# 05_kbd_pm.net
KiCad netlist of a schematic drawn in Altium Designer
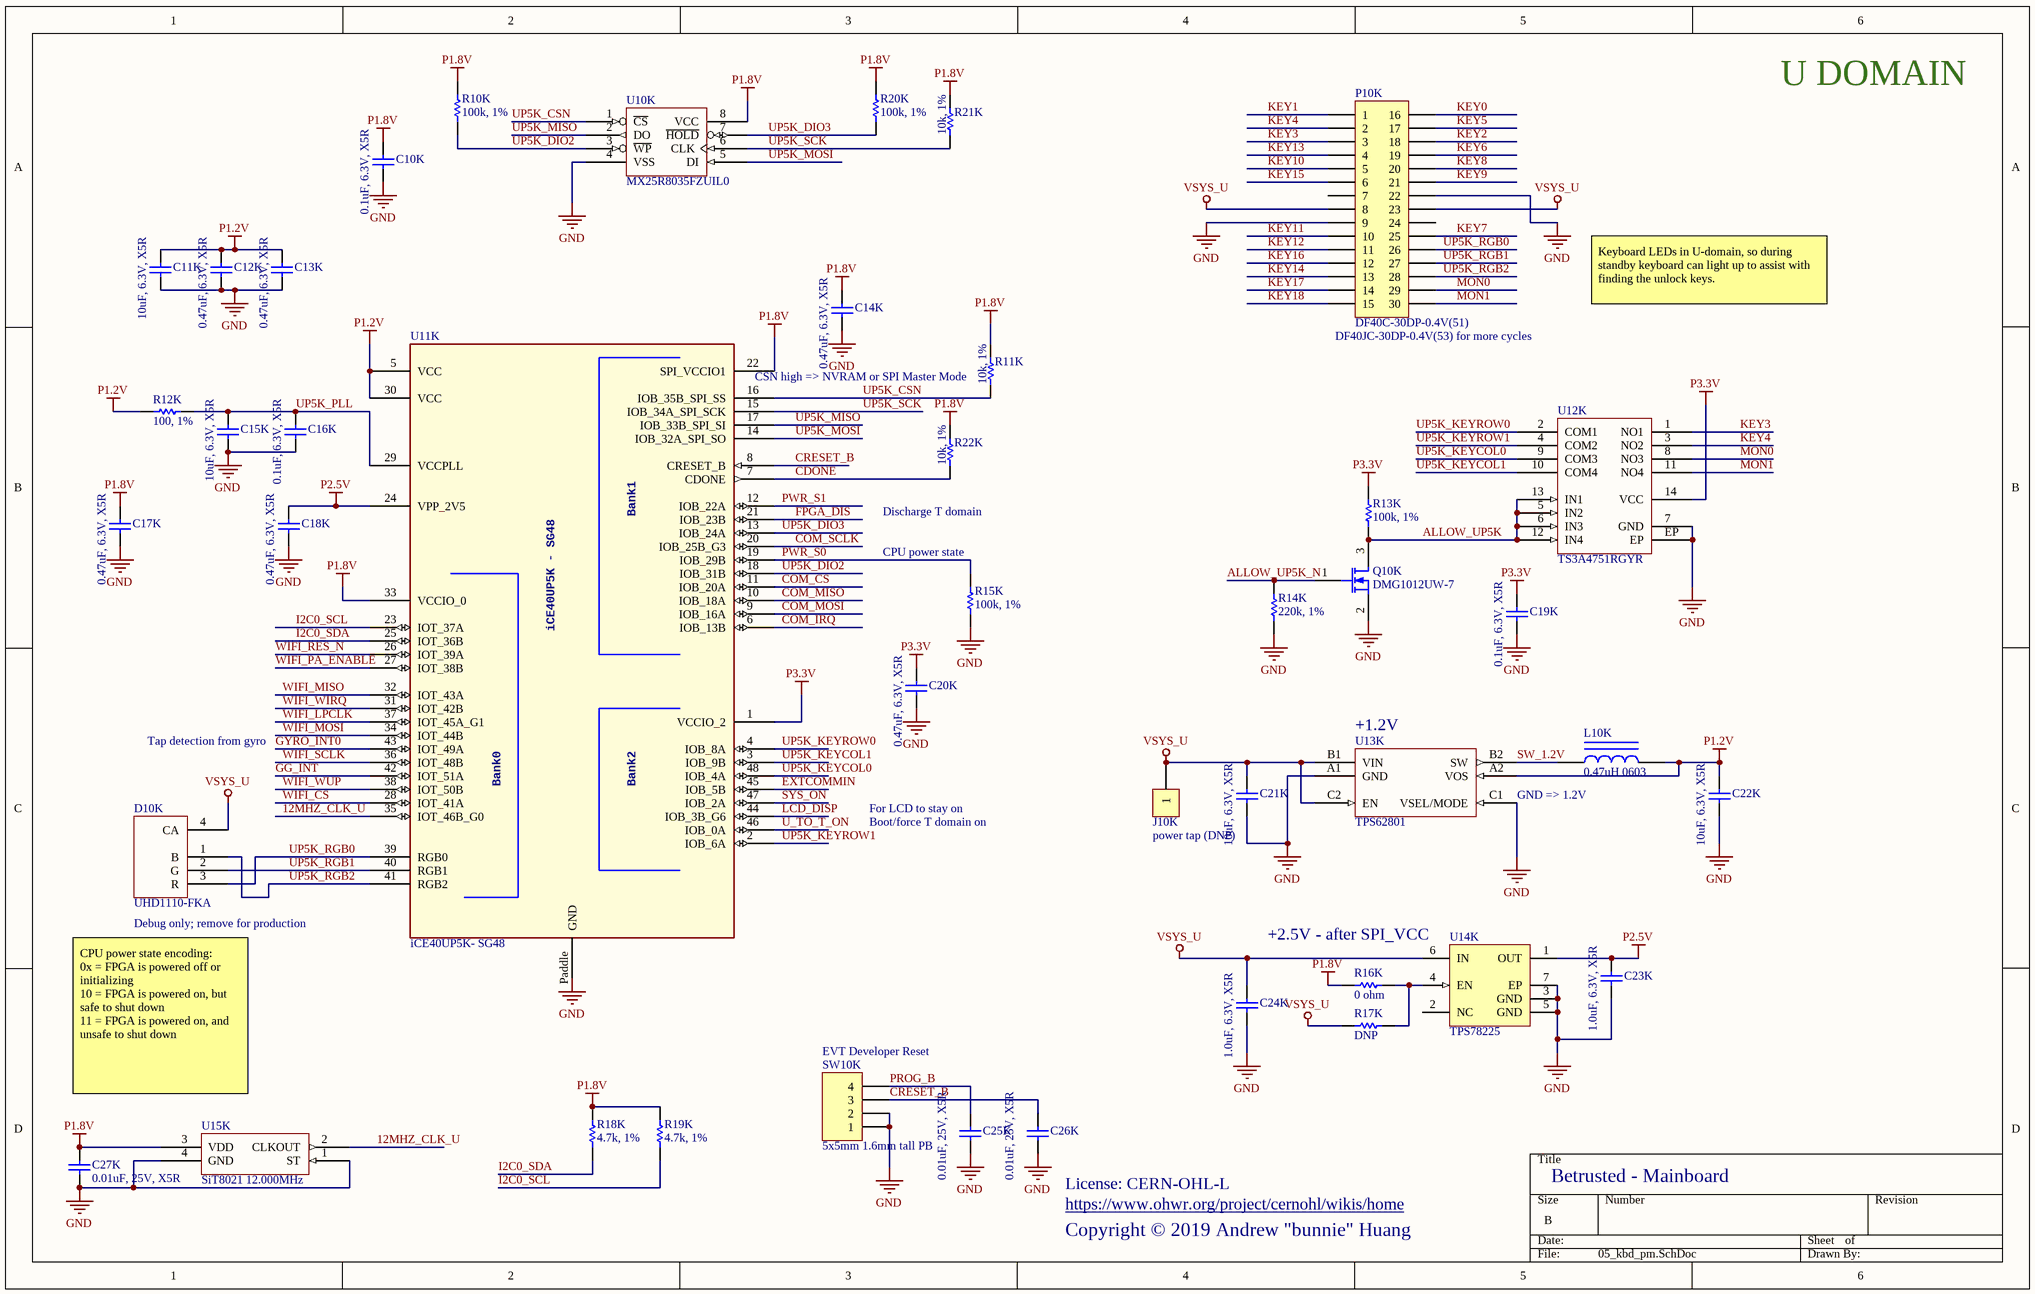
[diagram p0: 05_kbd_pm.SchDoc]

(export (version "E")
  (design (tool "Eeschema 10.0.6"))
  (components
    (comp (ref "C10K")
      (value "0.1uF, 6.3V, X5R")
      (footprint "B_CAP0201")
      (description "Capacitor (Semiconductor SIM Model)")
      (fields (field (name "MPN") "CL03A104KQ3NNNC"))
      (libsource (lib "Miscellaneous Devices") (part "Cap Semi"))
    )
    (comp (ref "C11K")
      (value "10uF, 6.3V, X5R")
      (footprint "B_CAP0603")
      (description "Capacitor (Semiconductor SIM Model)")
      (fields (field (name "MPN") "CL10A106MQ8NNNC"))
      (libsource (lib "Miscellaneous Devices") (part "Cap Semi"))
    )
    (comp (ref "C12K")
      (value "0.47uF, 6.3V, X5R")
      (footprint "B_CAP0201")
      (description "Capacitor (Semiconductor SIM Model)")
      (fields (field (name "MPN") "CL03A474KQ3NNNH"))
      (libsource (lib "Miscellaneous Devices") (part "Cap Semi"))
    )
    (comp (ref "C13K")
      (value "0.47uF, 6.3V, X5R")
      (footprint "B_CAP0201")
      (description "Capacitor (Semiconductor SIM Model)")
      (fields (field (name "MPN") "CL03A474KQ3NNNH"))
      (libsource (lib "Miscellaneous Devices") (part "Cap Semi"))
    )
    (comp (ref "C14K")
      (value "0.47uF, 6.3V, X5R")
      (footprint "B_CAP0201")
      (description "Capacitor (Semiconductor SIM Model)")
      (fields (field (name "MPN") "CL03A474KQ3NNNH"))
      (libsource (lib "Miscellaneous Devices") (part "Cap Semi"))
    )
    (comp (ref "C15K")
      (value "10uF, 6.3V, X5R")
      (footprint "B_CAP0603")
      (description "Capacitor (Semiconductor SIM Model)")
      (fields (field (name "MPN") "CL10A106MQ8NNNC"))
      (libsource (lib "Miscellaneous Devices") (part "Cap Semi"))
    )
    (comp (ref "C16K")
      (value "0.1uF, 6.3V, X5R")
      (footprint "B_CAP0201")
      (description "Capacitor (Semiconductor SIM Model)")
      (fields (field (name "MPN") "CL03A104KQ3NNNC"))
      (libsource (lib "Miscellaneous Devices") (part "Cap Semi"))
    )
    (comp (ref "C17K")
      (value "0.47uF, 6.3V, X5R")
      (footprint "B_CAP0201")
      (description "Capacitor (Semiconductor SIM Model)")
      (fields (field (name "MPN") "CL03A474KQ3NNNH"))
      (libsource (lib "Miscellaneous Devices") (part "Cap Semi"))
    )
    (comp (ref "C18K")
      (value "0.47uF, 6.3V, X5R")
      (footprint "B_CAP0201")
      (description "Capacitor (Semiconductor SIM Model)")
      (fields (field (name "MPN") "CL03A474KQ3NNNH"))
      (libsource (lib "Miscellaneous Devices") (part "Cap Semi"))
    )
    (comp (ref "C19K")
      (value "0.1uF, 6.3V, X5R")
      (footprint "B_CAP0201")
      (description "Capacitor (Semiconductor SIM Model)")
      (fields (field (name "MPN") "CL03A104KQ3NNNC"))
      (libsource (lib "Miscellaneous Devices") (part "Cap Semi"))
    )
    (comp (ref "C20K")
      (value "0.47uF, 6.3V, X5R")
      (footprint "B_CAP0201")
      (description "Capacitor (Semiconductor SIM Model)")
      (fields (field (name "MPN") "CL03A474KQ3NNNH"))
      (libsource (lib "Miscellaneous Devices") (part "Cap Semi"))
    )
    (comp (ref "C21K")
      (value "10uF, 6.3V, X5R")
      (footprint "B_CAP0603")
      (description "Capacitor (Semiconductor SIM Model)")
      (fields (field (name "MPN") "CL10A106MQ8NNNC"))
      (libsource (lib "Miscellaneous Devices") (part "Cap Semi"))
    )
    (comp (ref "C22K")
      (value "10uF, 6.3V, X5R")
      (footprint "B_CAP0603")
      (description "Capacitor (Semiconductor SIM Model)")
      (fields (field (name "MPN") "CL10A106MQ8NNNC"))
      (libsource (lib "Miscellaneous Devices") (part "Cap Semi"))
    )
    (comp (ref "C23K")
      (value "1.0uF, 6.3V, X5R")
      (footprint "B_CAP0201")
      (description "Capacitor (Semiconductor SIM Model)")
      (fields (field (name "MPN") "GRM033R60J105MEA2D"))
      (libsource (lib "Miscellaneous Devices") (part "Cap Semi"))
    )
    (comp (ref "C24K")
      (value "1.0uF, 6.3V, X5R")
      (footprint "B_CAP0201")
      (description "Capacitor (Semiconductor SIM Model)")
      (fields (field (name "MPN") "GRM033R60J105MEA2D"))
      (libsource (lib "Miscellaneous Devices") (part "Cap Semi"))
    )
    (comp (ref "C25K")
      (value "0.01uF, 25V, X5R")
      (footprint "B_RES0201")
      (description "Capacitor (Semiconductor SIM Model)")
      (fields (field (name "MPN") "GRM033R61E103KA12D"))
      (libsource (lib "Miscellaneous Devices") (part "Cap Semi"))
    )
    (comp (ref "C26K")
      (value "0.01uF, 25V, X5R")
      (footprint "B_RES0201")
      (description "Capacitor (Semiconductor SIM Model)")
      (fields (field (name "MPN") "GRM033R61E103KA12D"))
      (libsource (lib "Miscellaneous Devices") (part "Cap Semi"))
    )
    (comp (ref "C27K")
      (value "0.01uF, 25V, X5R")
      (footprint "B_RES0201")
      (description "Capacitor (Semiconductor SIM Model)")
      (fields (field (name "MPN") "GRM033R61E103KA12D"))
      (libsource (lib "Miscellaneous Devices") (part "Cap Semi"))
    )
    (comp (ref "D10K")
      (value "UHD1110-FKA")
      (footprint "CREE_UHD1110-FKA")
      (description "1x1mm SMD RGB LED, 5mA, common anode")
      (fields (field (name "MPN") "UHD1110-FKA-CL1A13R3Q1BBQFMF3"))
      (libsource (lib "commonsch-new") (part "CREE_UHD1110-FKA"))
    )
    (comp (ref "J10K")
      (value "power tap (DNP)")
      (footprint "RESTAP-0603")
      (description "Connector")
      (fields (field (name "MPN") "DNP"))
      (libsource (lib "*") (part "CON1"))
    )
    (comp (ref "L10K")
      (value "0.47uH 0603")
      (footprint "B_IND0603")
      (description "Magnetic-Core Inductor")
      (fields (field (name "MPN") "TFM160808ALC-R47MTAA"))
      (libsource (lib "Miscellaneous Devices") (part "Inductor Iron"))
    )
    (comp (ref "P10K")
      (value "DF40C-30DP-0.4V(51)")
      (footprint "HRS_DF40C-30DP-0.4V(51)")
      (description "Header, 15-Pin, Dual row")
      (fields (field (name "PUBLISHER") "Altium Limited"))
      (libsource (lib "Miscellaneous Connectors") (part "Header 15X2A"))
    )
    (comp (ref "Q10K")
      (value "DMG1012UW-7")
      (footprint "SOT323-3AN")
      (description "N-Channel MOSFET")
      (fields (field (name "PUBLISHER") "Altium Limited"))
      (libsource (lib "Miscellaneous Devices") (part "MOSFET-N"))
    )
    (comp (ref "R10K")
      (value "100k, 1%")
      (footprint "B_RES0201")
      (description "Resistor")
      (fields (field (name "MPN") "ANY"))
      (libsource (lib "Miscellaneous Devices") (part "Res1"))
    )
    (comp (ref "R11K")
      (value "10k, 1%")
      (footprint "B_RES0201")
      (description "Resistor")
      (fields (field (name "MPN") "ANY"))
      (libsource (lib "Miscellaneous Devices") (part "Res1"))
    )
    (comp (ref "R12K")
      (value "100, 1%")
      (footprint "B_RES0402")
      (description "Resistor")
      (fields (field (name "MPN") "ANY"))
      (libsource (lib "Miscellaneous Devices") (part "Res1"))
    )
    (comp (ref "R13K")
      (value "100k, 1%")
      (footprint "B_RES0201")
      (description "Resistor")
      (fields (field (name "MPN") "ANY"))
      (libsource (lib "Miscellaneous Devices") (part "Res1"))
    )
    (comp (ref "R14K")
      (value "220k, 1%")
      (footprint "B_RES0201")
      (description "Resistor")
      (fields (field (name "MPN") "ANY"))
      (libsource (lib "Miscellaneous Devices") (part "Res1"))
    )
    (comp (ref "R15K")
      (value "100k, 1%")
      (footprint "B_RES0201")
      (description "Resistor")
      (fields (field (name "MPN") "ANY"))
      (libsource (lib "Miscellaneous Devices") (part "Res1"))
    )
    (comp (ref "R16K")
      (value "0 ohm")
      (footprint "B_RES0201")
      (description "Resistor")
      (fields (field (name "MPN") "ANY"))
      (libsource (lib "Miscellaneous Devices") (part "Res1"))
    )
    (comp (ref "R17K")
      (value "DNP")
      (footprint "B_RES0201")
      (description "Resistor")
      (fields (field (name "MPN") "ANY"))
      (libsource (lib "Miscellaneous Devices") (part "Res1"))
    )
    (comp (ref "R18K")
      (value "4.7k, 1%")
      (footprint "B_RES0201")
      (description "Resistor")
      (fields (field (name "MPN") "ANY"))
      (libsource (lib "Miscellaneous Devices") (part "Res1"))
    )
    (comp (ref "R19K")
      (value "4.7k, 1%")
      (footprint "B_RES0201")
      (description "Resistor")
      (fields (field (name "MPN") "ANY"))
      (libsource (lib "Miscellaneous Devices") (part "Res1"))
    )
    (comp (ref "R20K")
      (value "100k, 1%")
      (footprint "B_RES0201")
      (description "Resistor")
      (fields (field (name "MPN") "ANY"))
      (libsource (lib "Miscellaneous Devices") (part "Res1"))
    )
    (comp (ref "R21K")
      (value "10k, 1%")
      (footprint "B_RES0201")
      (description "Resistor")
      (fields (field (name "MPN") "ANY"))
      (libsource (lib "Miscellaneous Devices") (part "Res1"))
    )
    (comp (ref "R22K")
      (value "10k, 1%")
      (footprint "B_RES0201")
      (description "Resistor")
      (fields (field (name "MPN") "ANY"))
      (libsource (lib "Miscellaneous Devices") (part "Res1"))
    )
    (comp (ref "SW10K")
      (value "5x5mm 1.6mm tall PB")
      (footprint "SWITCH_TS-1187A")
      (description "Chi Fung TS-1187A")
      (fields (field (name "MPN") "RS-187R05A2-DS MT RT") (field (name "PUBLISHER") "Altium Limited"))
      (libsource (lib "Miscellaneous Connectors") (part "Header 4"))
    )
    (comp (ref "U10K")
      (value "MX25R8035FZUIL0")
      (footprint "USON-8")
      (description "64Mbit SPI NOR FLASH")
      (libsource (lib "commonsch") (part "EN25P05-50GCP"))
    )
    (comp (ref "U11K")
      (value "iCE40UP5K- SG48")
      (footprint "UP5K_QFN127P600-8N")
      (libsource (lib "LATTICEPLDS_Library") (part "iCE40UP5K- SG48"))
    )
    (comp (ref "U12K")
      (value "TS3A4751RGYR")
      (footprint "TI_RGY_S_PVQFN-N14")
      (description "0.9 ohm low voltage, single supply, 4-channel SPST analog switch")
      (libsource (lib "commonsch-new") (part "TS3A4751RGYR"))
    )
    (comp (ref "U13K")
      (value "TPS62801")
      (footprint "BGA6C35P2X3_70X105X40_NSMD")
      (description "Buck regulator, 4MHz, 0.6A, 0.8V-1.55V, low Iq")
      (fields (field (name "MPN") "TPS62801YKAT"))
      (libsource (lib "altium-import") (part "root_0_TPS62801_"))
    )
    (comp (ref "U14K")
      (value "TPS78225")
      (footprint "TI-DRV6-1600X1000TP_V")
      (description "500nA Iq, 150mA LDO")
      (fields (field (name "MPN") "TPS78225DRVT"))
      (libsource (lib "TI-TPS78225-Q1DRV6-1600X1000TP") (part "TI-TPS78225-Q1DRV6-1600X1000TP"))
    )
    (comp (ref "U15K")
      (value "SiT8021 12.000MHz")
      (footprint "SiTIME_CSP")
      (description "1 to 26 MHz micropower oscillator")
      (fields (field (name "MPN") "SIT8021AI-J4-18S-12.000000E"))
      (libsource (lib "altium-import") (part "root_2_SiT8021_"))
    )
  )
  (nets
    (net (code "1") (name "/12MHZ_CLK_U") (class "Default")
      (node (ref "U11K") (pin "35") (pinfunction "IOT_46B_G0_35") (pintype "bidirectional"))
      (node (ref "U15K") (pin "2") (pinfunction "CLKOUT_2") (pintype "output"))
    )
    (net (code "2") (name "/ALLOW_UP5K") (class "Default")
      (node (ref "Q10K") (pin "3") (pinfunction "D_3") (pintype "passive"))
      (node (ref "R13K") (pin "1") (pinfunction "1_1") (pintype "passive"))
      (node (ref "U12K") (pin "12") (pinfunction "IN4_12") (pintype "input"))
      (node (ref "U12K") (pin "13") (pinfunction "IN1_13") (pintype "input"))
      (node (ref "U12K") (pin "5") (pinfunction "IN2_5") (pintype "input"))
      (node (ref "U12K") (pin "6") (pinfunction "IN3_6") (pintype "input"))
    )
    (net (code "3") (name "/ALLOW_UP5K_N") (class "Default")
      (node (ref "Q10K") (pin "1") (pinfunction "G_1") (pintype "passive"))
      (node (ref "R14K") (pin "2") (pinfunction "2_2") (pintype "passive"))
    )
    (net (code "4") (name "/CDONE") (class "Default")
      (node (ref "R22K") (pin "2") (pinfunction "2_2") (pintype "passive"))
      (node (ref "U11K") (pin "7") (pinfunction "CDONE_7") (pintype "output"))
    )
    (net (code "5") (name "/COM_CS") (class "Default")
      (node (ref "U11K") (pin "11") (pinfunction "IOB_20A_11") (pintype "bidirectional"))
    )
    (net (code "6") (name "/COM_IRQ") (class "Default")
      (node (ref "U11K") (pin "6") (pinfunction "IOB_13B_6") (pintype "bidirectional"))
    )
    (net (code "7") (name "/COM_MISO") (class "Default")
      (node (ref "U11K") (pin "10") (pinfunction "IOB_18A_10") (pintype "bidirectional"))
    )
    (net (code "8") (name "/COM_MOSI") (class "Default")
      (node (ref "U11K") (pin "9") (pinfunction "IOB_16A_9") (pintype "bidirectional"))
    )
    (net (code "9") (name "/COM_SCLK") (class "Default")
      (node (ref "U11K") (pin "20") (pinfunction "IOB_25B_G3_20") (pintype "bidirectional"))
    )
    (net (code "10") (name "/CRESET_B") (class "Default")
      (node (ref "C26K") (pin "1") (pinfunction "1_1") (pintype "passive"))
      (node (ref "SW10K") (pin "3") (pinfunction "3_3") (pintype "passive"))
      (node (ref "U11K") (pin "8") (pinfunction "CRESET_B_8") (pintype "input"))
    )
    (net (code "11") (name "/EXTCOMMIN") (class "Default")
      (node (ref "U11K") (pin "45") (pinfunction "IOB_5B_45") (pintype "bidirectional"))
    )
    (net (code "12") (name "/FPGA_DIS") (class "Default")
      (node (ref "U11K") (pin "21") (pinfunction "IOB_23B_21") (pintype "bidirectional"))
    )
    (net (code "13") (name "/GG_INT") (class "Default")
      (node (ref "U11K") (pin "42") (pinfunction "IOT_51A_42") (pintype "bidirectional"))
    )
    (net (code "14") (name "/GYRO_INT0") (class "Default")
      (node (ref "U11K") (pin "43") (pinfunction "IOT_49A_43") (pintype "bidirectional"))
    )
    (net (code "15") (name "/I2C0_SCL") (class "Default")
      (node (ref "R19K") (pin "1") (pinfunction "1_1") (pintype "passive"))
      (node (ref "U11K") (pin "23") (pinfunction "IOT_37A_23") (pintype "bidirectional"))
    )
    (net (code "16") (name "/I2C0_SDA") (class "Default")
      (node (ref "R18K") (pin "1") (pinfunction "1_1") (pintype "passive"))
      (node (ref "U11K") (pin "25") (pinfunction "IOT_36B_25") (pintype "bidirectional"))
    )
    (net (code "17") (name "/KEY0") (class "Default")
      (node (ref "P10K") (pin "16") (pinfunction "16_16") (pintype "passive"))
    )
    (net (code "18") (name "/KEY1") (class "Default")
      (node (ref "P10K") (pin "1") (pinfunction "1_1") (pintype "passive"))
    )
    (net (code "19") (name "/KEY2") (class "Default")
      (node (ref "P10K") (pin "18") (pinfunction "18_18") (pintype "passive"))
    )
    (net (code "20") (name "/KEY3") (class "Default")
      (node (ref "P10K") (pin "3") (pinfunction "3_3") (pintype "passive"))
      (node (ref "U12K") (pin "1") (pinfunction "NO1_1") (pintype "passive"))
    )
    (net (code "21") (name "/KEY4") (class "Default")
      (node (ref "P10K") (pin "2") (pinfunction "2_2") (pintype "passive"))
      (node (ref "U12K") (pin "3") (pinfunction "NO2_3") (pintype "passive"))
    )
    (net (code "22") (name "/KEY5") (class "Default")
      (node (ref "P10K") (pin "17") (pinfunction "17_17") (pintype "passive"))
    )
    (net (code "23") (name "/KEY6") (class "Default")
      (node (ref "P10K") (pin "19") (pinfunction "19_19") (pintype "passive"))
    )
    (net (code "24") (name "/KEY7") (class "Default")
      (node (ref "P10K") (pin "25") (pinfunction "25_25") (pintype "passive"))
    )
    (net (code "25") (name "/KEY8") (class "Default")
      (node (ref "P10K") (pin "20") (pinfunction "20_20") (pintype "passive"))
    )
    (net (code "26") (name "/KEY9") (class "Default")
      (node (ref "P10K") (pin "21") (pinfunction "21_21") (pintype "passive"))
    )
    (net (code "27") (name "/KEY10") (class "Default")
      (node (ref "P10K") (pin "5") (pinfunction "5_5") (pintype "passive"))
    )
    (net (code "28") (name "/KEY11") (class "Default")
      (node (ref "P10K") (pin "10") (pinfunction "10_10") (pintype "passive"))
    )
    (net (code "29") (name "/KEY12") (class "Default")
      (node (ref "P10K") (pin "11") (pinfunction "11_11") (pintype "passive"))
    )
    (net (code "30") (name "/KEY13") (class "Default")
      (node (ref "P10K") (pin "4") (pinfunction "4_4") (pintype "passive"))
    )
    (net (code "31") (name "/KEY14") (class "Default")
      (node (ref "P10K") (pin "13") (pinfunction "13_13") (pintype "passive"))
    )
    (net (code "32") (name "/KEY15") (class "Default")
      (node (ref "P10K") (pin "6") (pinfunction "6_6") (pintype "passive"))
    )
    (net (code "33") (name "/KEY16") (class "Default")
      (node (ref "P10K") (pin "12") (pinfunction "12_12") (pintype "passive"))
    )
    (net (code "34") (name "/KEY17") (class "Default")
      (node (ref "P10K") (pin "14") (pinfunction "14_14") (pintype "passive"))
    )
    (net (code "35") (name "/KEY18") (class "Default")
      (node (ref "P10K") (pin "15") (pinfunction "15_15") (pintype "passive"))
    )
    (net (code "36") (name "/LCD_DISP") (class "Default")
      (node (ref "U11K") (pin "44") (pinfunction "IOB_3B_G6_44") (pintype "bidirectional"))
    )
    (net (code "37") (name "/MON0") (class "Default")
      (node (ref "P10K") (pin "29") (pinfunction "29_29") (pintype "passive"))
      (node (ref "U12K") (pin "8") (pinfunction "NO3_8") (pintype "passive"))
    )
    (net (code "38") (name "/MON1") (class "Default")
      (node (ref "P10K") (pin "30") (pinfunction "30_30") (pintype "passive"))
      (node (ref "U12K") (pin "11") (pinfunction "NO4_11") (pintype "passive"))
    )
    (net (code "39") (name "/PROG_B") (class "Default")
      (node (ref "C25K") (pin "1") (pinfunction "1_1") (pintype "passive"))
      (node (ref "SW10K") (pin "4") (pinfunction "4_4") (pintype "passive"))
    )
    (net (code "40") (name "/PWR_S0") (class "Default")
      (node (ref "R15K") (pin "2") (pinfunction "2_2") (pintype "passive"))
      (node (ref "U11K") (pin "19") (pinfunction "IOB_29B_19") (pintype "bidirectional"))
    )
    (net (code "41") (name "/PWR_S1") (class "Default")
      (node (ref "U11K") (pin "12") (pinfunction "IOB_22A_12") (pintype "bidirectional"))
    )
    (net (code "42") (name "/SW_1.2V") (class "Default")
      (node (ref "L10K") (pin "1") (pinfunction "1_1") (pintype "passive"))
      (node (ref "U13K") (pin "B2") (pinfunction "SW_B2") (pintype "output"))
    )
    (net (code "43") (name "/SYS_ON") (class "Default")
      (node (ref "U11K") (pin "47") (pinfunction "IOB_2A_47") (pintype "bidirectional"))
    )
    (net (code "44") (name "/UP5K_CSN") (class "Default")
      (node (ref "R11K") (pin "2") (pinfunction "2_2") (pintype "passive"))
      (node (ref "U10K") (pin "1") (pinfunction "~{CS}_1") (pintype "input"))
      (node (ref "U11K") (pin "16") (pinfunction "IOB_35B_SPI_SS_16") (pintype "passive"))
    )
    (net (code "45") (name "/UP5K_DIO2") (class "Default")
      (node (ref "R10K") (pin "1") (pinfunction "1_1") (pintype "passive"))
      (node (ref "U10K") (pin "3") (pinfunction "~{WP}_3") (pintype "input"))
      (node (ref "U11K") (pin "18") (pinfunction "IOB_31B_18") (pintype "bidirectional"))
    )
    (net (code "46") (name "/UP5K_DIO3") (class "Default")
      (node (ref "R20K") (pin "1") (pinfunction "1_1") (pintype "passive"))
      (node (ref "U10K") (pin "7") (pinfunction "~{HOLD}_7") (pintype "bidirectional"))
      (node (ref "U11K") (pin "13") (pinfunction "IOB_24A_13") (pintype "bidirectional"))
    )
    (net (code "47") (name "/UP5K_KEYCOL0") (class "Default")
      (node (ref "U11K") (pin "48") (pinfunction "IOB_4A_48") (pintype "bidirectional"))
      (node (ref "U12K") (pin "9") (pinfunction "COM3_9") (pintype "passive"))
    )
    (net (code "48") (name "/UP5K_KEYCOL1") (class "Default")
      (node (ref "U11K") (pin "3") (pinfunction "IOB_9B_3") (pintype "bidirectional"))
      (node (ref "U12K") (pin "10") (pinfunction "COM4_10") (pintype "passive"))
    )
    (net (code "49") (name "/UP5K_KEYROW0") (class "Default")
      (node (ref "U11K") (pin "4") (pinfunction "IOB_8A_4") (pintype "bidirectional"))
      (node (ref "U12K") (pin "2") (pinfunction "COM1_2") (pintype "passive"))
    )
    (net (code "50") (name "/UP5K_KEYROW1") (class "Default")
      (node (ref "U11K") (pin "2") (pinfunction "IOB_6A_2") (pintype "bidirectional"))
      (node (ref "U12K") (pin "4") (pinfunction "COM2_4") (pintype "passive"))
    )
    (net (code "51") (name "/UP5K_MISO") (class "Default")
      (node (ref "U10K") (pin "2") (pinfunction "DO_2") (pintype "output"))
      (node (ref "U11K") (pin "17") (pinfunction "IOB_33B_SPI_SI_17") (pintype "passive"))
    )
    (net (code "52") (name "/UP5K_MOSI") (class "Default")
      (node (ref "U10K") (pin "5") (pinfunction "DI_5") (pintype "input"))
      (node (ref "U11K") (pin "14") (pinfunction "IOB_32A_SPI_SO_14") (pintype "passive"))
    )
    (net (code "53") (name "/UP5K_PLL") (class "Default")
      (node (ref "C15K") (pin "1") (pinfunction "1_1") (pintype "passive"))
      (node (ref "C16K") (pin "1") (pinfunction "1_1") (pintype "passive"))
      (node (ref "R12K") (pin "1") (pinfunction "1_1") (pintype "passive"))
      (node (ref "U11K") (pin "29") (pinfunction "VCCPLL_29") (pintype "power_in"))
    )
    (net (code "54") (name "/UP5K_RGB0") (class "Default")
      (node (ref "D10K") (pin "3") (pinfunction "R_3") (pintype "passive"))
      (node (ref "P10K") (pin "26") (pinfunction "26_26") (pintype "passive"))
      (node (ref "U11K") (pin "39") (pinfunction "RGB0_39") (pintype "open_collector"))
    )
    (net (code "55") (name "/UP5K_RGB1") (class "Default")
      (node (ref "D10K") (pin "2") (pinfunction "G_2") (pintype "passive"))
      (node (ref "P10K") (pin "27") (pinfunction "27_27") (pintype "passive"))
      (node (ref "U11K") (pin "40") (pinfunction "RGB1_40") (pintype "open_collector"))
    )
    (net (code "56") (name "/UP5K_RGB2") (class "Default")
      (node (ref "D10K") (pin "1") (pinfunction "B_1") (pintype "passive"))
      (node (ref "P10K") (pin "28") (pinfunction "28_28") (pintype "passive"))
      (node (ref "U11K") (pin "41") (pinfunction "RGB2_41") (pintype "open_collector"))
    )
    (net (code "57") (name "/UP5K_SCK") (class "Default")
      (node (ref "R21K") (pin "2") (pinfunction "2_2") (pintype "passive"))
      (node (ref "U10K") (pin "6") (pinfunction "CLK_6") (pintype "input"))
      (node (ref "U11K") (pin "15") (pinfunction "IOB_34A_SPI_SCK_15") (pintype "passive"))
    )
    (net (code "58") (name "/U_TO_T_ON") (class "Default")
      (node (ref "U11K") (pin "46") (pinfunction "IOB_0A_46") (pintype "bidirectional"))
    )
    (net (code "59") (name "/WIFI_CS") (class "Default")
      (node (ref "U11K") (pin "28") (pinfunction "IOT_41A_28") (pintype "bidirectional"))
    )
    (net (code "60") (name "/WIFI_LPCLK") (class "Default")
      (node (ref "U11K") (pin "37") (pinfunction "IOT_45A_G1_37") (pintype "bidirectional"))
    )
    (net (code "61") (name "/WIFI_MISO") (class "Default")
      (node (ref "U11K") (pin "32") (pinfunction "IOT_43A_32") (pintype "bidirectional"))
    )
    (net (code "62") (name "/WIFI_MOSI") (class "Default")
      (node (ref "U11K") (pin "34") (pinfunction "IOT_44B_34") (pintype "bidirectional"))
    )
    (net (code "63") (name "/WIFI_PA_ENABLE") (class "Default")
      (node (ref "U11K") (pin "27") (pinfunction "IOT_38B_27") (pintype "bidirectional"))
    )
    (net (code "64") (name "/WIFI_RES_N") (class "Default")
      (node (ref "U11K") (pin "26") (pinfunction "IOT_39A_26") (pintype "bidirectional"))
    )
    (net (code "65") (name "/WIFI_SCLK") (class "Default")
      (node (ref "U11K") (pin "36") (pinfunction "IOT_48B_36") (pintype "bidirectional"))
    )
    (net (code "66") (name "/WIFI_WIRQ") (class "Default")
      (node (ref "U11K") (pin "31") (pinfunction "IOT_42B_31") (pintype "bidirectional"))
    )
    (net (code "67") (name "/WIFI_WUP") (class "Default")
      (node (ref "U11K") (pin "38") (pinfunction "IOT_50B_38") (pintype "bidirectional"))
    )
    (net (code "68") (name "GND") (class "Default")
      (node (ref "C10K") (pin "2") (pinfunction "2_2") (pintype "passive"))
      (node (ref "C11K") (pin "2") (pinfunction "2_2") (pintype "passive"))
      (node (ref "C12K") (pin "2") (pinfunction "2_2") (pintype "passive"))
      (node (ref "C13K") (pin "2") (pinfunction "2_2") (pintype "passive"))
      (node (ref "C14K") (pin "2") (pinfunction "2_2") (pintype "passive"))
      (node (ref "C15K") (pin "2") (pinfunction "2_2") (pintype "passive"))
      (node (ref "C16K") (pin "2") (pinfunction "2_2") (pintype "passive"))
      (node (ref "C17K") (pin "2") (pinfunction "2_2") (pintype "passive"))
      (node (ref "C18K") (pin "2") (pinfunction "2_2") (pintype "passive"))
      (node (ref "C19K") (pin "2") (pinfunction "2_2") (pintype "passive"))
      (node (ref "C20K") (pin "2") (pinfunction "2_2") (pintype "passive"))
      (node (ref "C21K") (pin "2") (pinfunction "2_2") (pintype "passive"))
      (node (ref "C22K") (pin "2") (pinfunction "2_2") (pintype "passive"))
      (node (ref "C23K") (pin "2") (pinfunction "2_2") (pintype "passive"))
      (node (ref "C24K") (pin "2") (pinfunction "2_2") (pintype "passive"))
      (node (ref "C25K") (pin "2") (pinfunction "2_2") (pintype "passive"))
      (node (ref "C26K") (pin "2") (pinfunction "2_2") (pintype "passive"))
      (node (ref "C27K") (pin "2") (pinfunction "2_2") (pintype "passive"))
      (node (ref "P10K") (pin "22") (pinfunction "22_22") (pintype "passive"))
      (node (ref "P10K") (pin "9") (pinfunction "9_9") (pintype "passive"))
      (node (ref "Q10K") (pin "2") (pinfunction "S_2") (pintype "passive"))
      (node (ref "R14K") (pin "1") (pinfunction "1_1") (pintype "passive"))
      (node (ref "R15K") (pin "1") (pinfunction "1_1") (pintype "passive"))
      (node (ref "SW10K") (pin "1") (pinfunction "1_1") (pintype "passive"))
      (node (ref "SW10K") (pin "2") (pinfunction "2_2") (pintype "passive"))
      (node (ref "U10K") (pin "4") (pinfunction "VSS_4") (pintype "power_in"))
      (node (ref "U11K") (pin "Paddle") (pinfunction "GND_Paddle") (pintype "power_in"))
      (node (ref "U12K") (pin "7") (pinfunction "GND_7") (pintype "power_in"))
      (node (ref "U12K") (pin "EP") (pinfunction "EP_EP") (pintype "power_in"))
      (node (ref "U13K") (pin "A1") (pinfunction "GND_A1") (pintype "power_in"))
      (node (ref "U13K") (pin "C1") (pinfunction "VSEL/MODE_C1") (pintype "input"))
      (node (ref "U14K") (pin "3") (pinfunction "GND_3") (pintype "power_in"))
      (node (ref "U14K") (pin "5") (pinfunction "GND_5") (pintype "power_in"))
      (node (ref "U14K") (pin "7") (pinfunction "EP_7") (pintype "power_in"))
      (node (ref "U15K") (pin "1") (pinfunction "ST_1") (pintype "input"))
      (node (ref "U15K") (pin "4") (pinfunction "GND_4") (pintype "power_in"))
    )
    (net (code "69") (name "Net-(U14K-EN)") (class "Default")
      (node (ref "R16K") (pin "2") (pinfunction "2_2") (pintype "passive"))
      (node (ref "R17K") (pin "2") (pinfunction "2_2") (pintype "passive"))
      (node (ref "U14K") (pin "4") (pinfunction "EN_4") (pintype "input"))
    )
    (net (code "70") (name "P1.2V") (class "Default")
      (node (ref "C11K") (pin "1") (pinfunction "1_1") (pintype "passive"))
      (node (ref "C12K") (pin "1") (pinfunction "1_1") (pintype "passive"))
      (node (ref "C13K") (pin "1") (pinfunction "1_1") (pintype "passive"))
      (node (ref "C22K") (pin "1") (pinfunction "1_1") (pintype "passive"))
      (node (ref "L10K") (pin "2") (pinfunction "2_2") (pintype "passive"))
      (node (ref "R12K") (pin "2") (pinfunction "2_2") (pintype "passive"))
      (node (ref "U11K") (pin "30") (pinfunction "VCC_30") (pintype "power_in"))
      (node (ref "U11K") (pin "5") (pinfunction "VCC_5") (pintype "power_in"))
      (node (ref "U13K") (pin "A2") (pinfunction "VOS_A2") (pintype "input"))
    )
    (net (code "71") (name "P1.8V") (class "Default")
      (node (ref "C10K") (pin "1") (pinfunction "1_1") (pintype "passive"))
      (node (ref "C14K") (pin "1") (pinfunction "1_1") (pintype "passive"))
      (node (ref "C17K") (pin "1") (pinfunction "1_1") (pintype "passive"))
      (node (ref "C27K") (pin "1") (pinfunction "1_1") (pintype "passive"))
      (node (ref "R10K") (pin "2") (pinfunction "2_2") (pintype "passive"))
      (node (ref "R11K") (pin "1") (pinfunction "1_1") (pintype "passive"))
      (node (ref "R16K") (pin "1") (pinfunction "1_1") (pintype "passive"))
      (node (ref "R18K") (pin "2") (pinfunction "2_2") (pintype "passive"))
      (node (ref "R19K") (pin "2") (pinfunction "2_2") (pintype "passive"))
      (node (ref "R20K") (pin "2") (pinfunction "2_2") (pintype "passive"))
      (node (ref "R21K") (pin "1") (pinfunction "1_1") (pintype "passive"))
      (node (ref "R22K") (pin "1") (pinfunction "1_1") (pintype "passive"))
      (node (ref "U10K") (pin "8") (pinfunction "VCC_8") (pintype "power_in"))
      (node (ref "U11K") (pin "22") (pinfunction "SPI_VCCIO1_22") (pintype "power_in"))
      (node (ref "U11K") (pin "33") (pinfunction "VCCIO_0_33") (pintype "power_in"))
      (node (ref "U15K") (pin "3") (pinfunction "VDD_3") (pintype "power_in"))
    )
    (net (code "72") (name "P2.5V") (class "Default")
      (node (ref "C18K") (pin "1") (pinfunction "1_1") (pintype "passive"))
      (node (ref "C23K") (pin "1") (pinfunction "1_1") (pintype "passive"))
      (node (ref "U11K") (pin "24") (pinfunction "VPP_2V5_24") (pintype "power_in"))
      (node (ref "U14K") (pin "1") (pinfunction "OUT_1") (pintype "power_in"))
    )
    (net (code "73") (name "P3.3V") (class "Default")
      (node (ref "C19K") (pin "1") (pinfunction "1_1") (pintype "passive"))
      (node (ref "C20K") (pin "1") (pinfunction "1_1") (pintype "passive"))
      (node (ref "R13K") (pin "2") (pinfunction "2_2") (pintype "passive"))
      (node (ref "U11K") (pin "1") (pinfunction "VCCIO_2_1") (pintype "power_in"))
      (node (ref "U12K") (pin "14") (pinfunction "VCC_14") (pintype "power_in"))
    )
    (net (code "74") (name "VSYS_U") (class "Default")
      (node (ref "C21K") (pin "1") (pinfunction "1_1") (pintype "passive"))
      (node (ref "C24K") (pin "1") (pinfunction "1_1") (pintype "passive"))
      (node (ref "D10K") (pin "4") (pinfunction "CA_4") (pintype "passive"))
      (node (ref "J10K") (pin "1") (pinfunction "1_1") (pintype "passive"))
      (node (ref "P10K") (pin "23") (pinfunction "23_23") (pintype "passive"))
      (node (ref "P10K") (pin "8") (pinfunction "8_8") (pintype "passive"))
      (node (ref "R17K") (pin "1") (pinfunction "1_1") (pintype "passive"))
      (node (ref "U13K") (pin "B1") (pinfunction "VIN_B1") (pintype "power_in"))
      (node (ref "U13K") (pin "C2") (pinfunction "EN_C2") (pintype "input"))
      (node (ref "U14K") (pin "6") (pinfunction "IN_6") (pintype "power_in"))
    )
    (net (code "75") (name "unconnected-(P10K-Pad7)") (class "Default")
      (node (ref "P10K") (pin "7") (pinfunction "7_7") (pintype "passive"))
    )
    (net (code "76") (name "unconnected-(P10K-Pad24)") (class "Default")
      (node (ref "P10K") (pin "24") (pinfunction "24_24") (pintype "passive"))
    )
    (net (code "77") (name "unconnected-(U14K-NC-Pad2)") (class "Default")
      (node (ref "U14K") (pin "2") (pinfunction "NC_2") (pintype "passive"))
    )
  )
)
